# 11ethernetGbit.net
KiCad netlist of a schematic drawn in Altium Designer
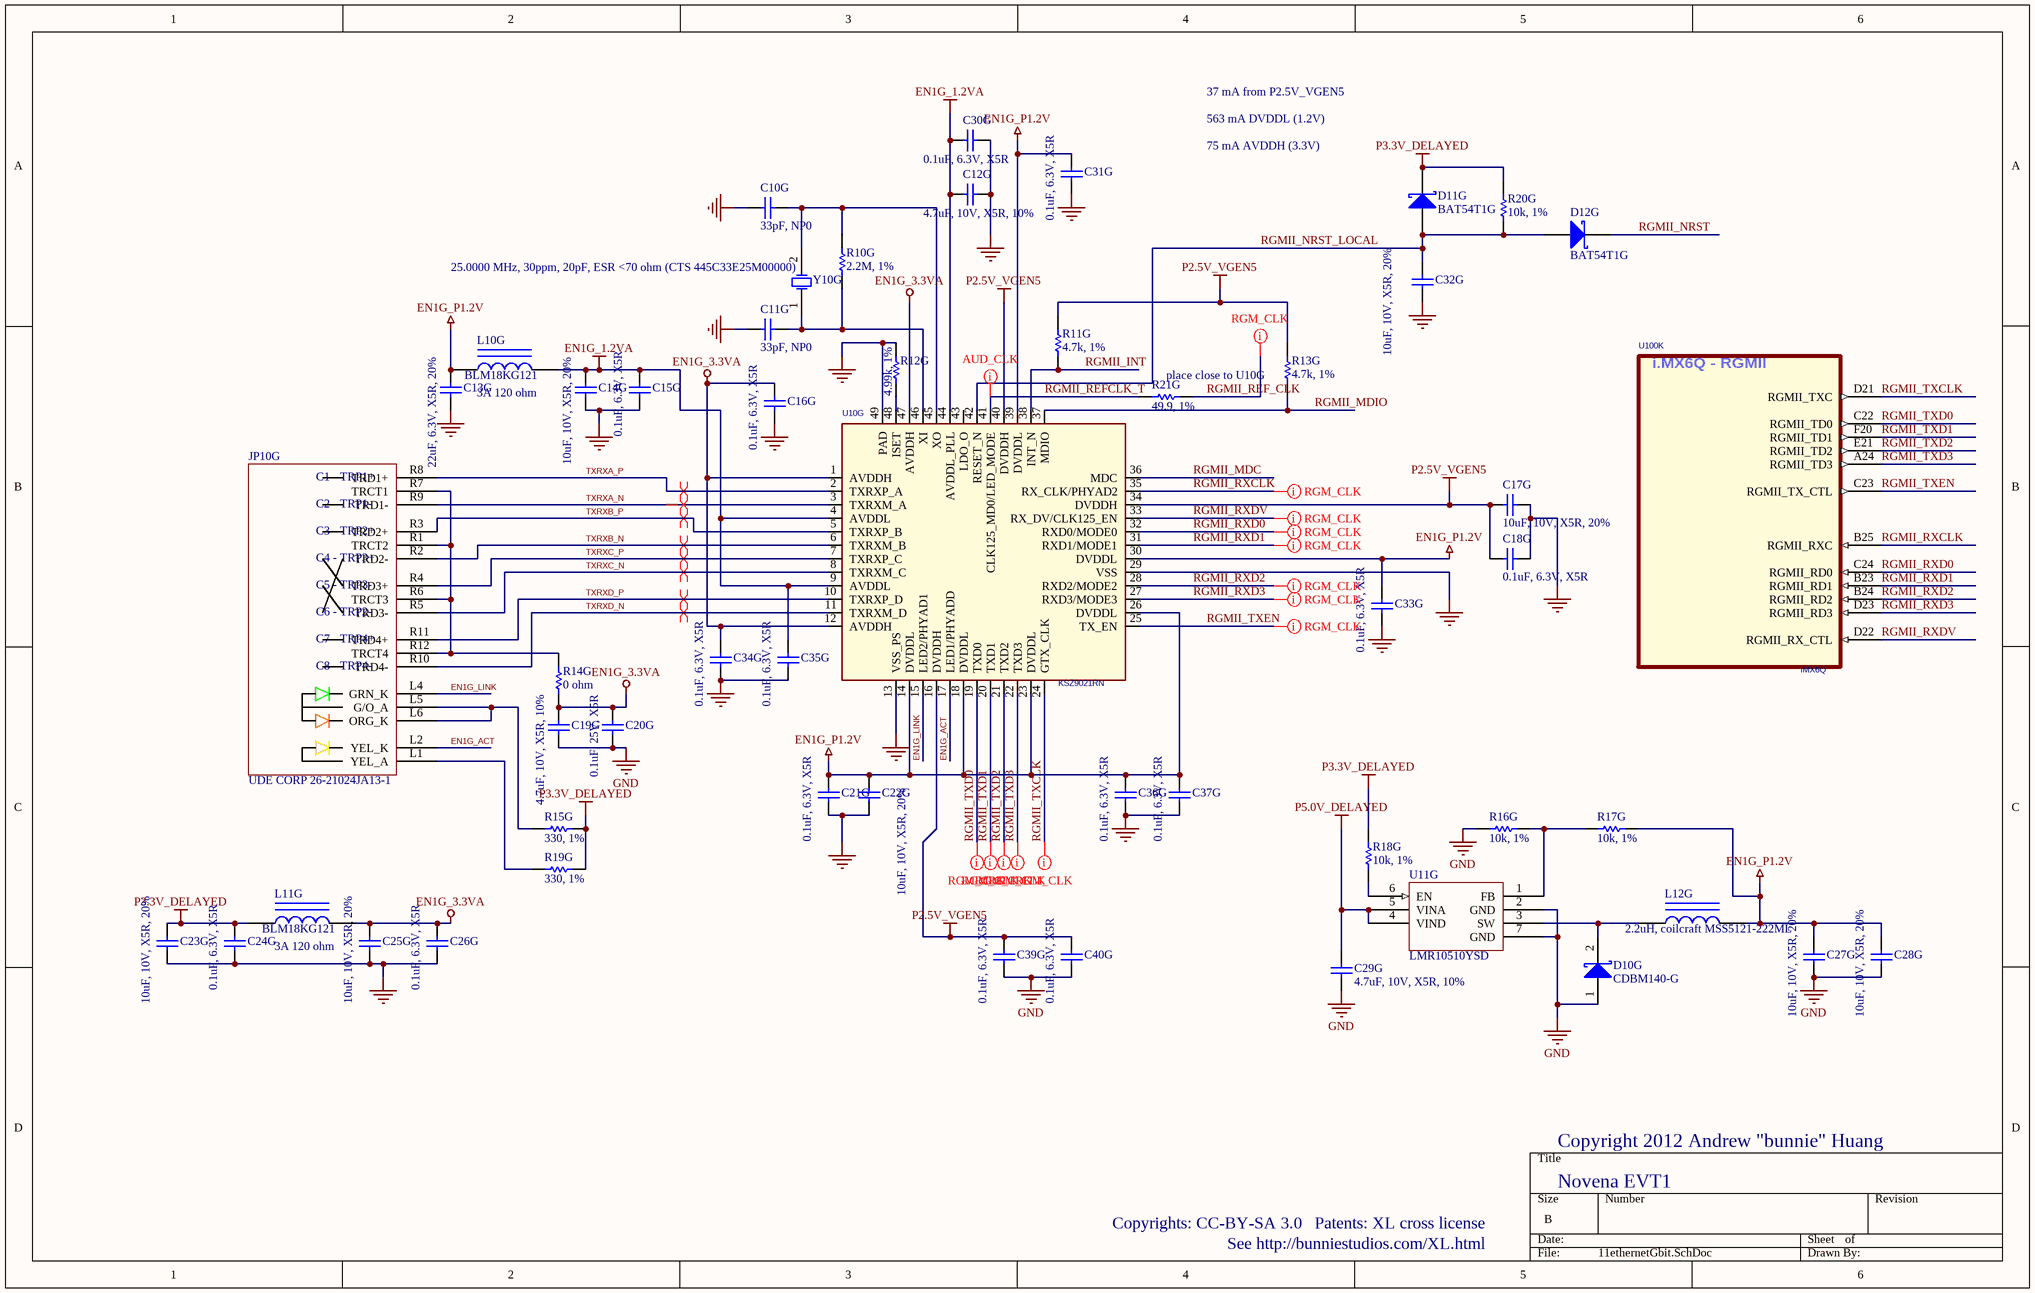
[diagram p0: 11ethernetGbit.SchDoc]

(export (version "E")
  (design (tool "Eeschema 10.0.6"))
  (components
    (comp (ref "C10G")
      (value "33pF, NP0")
      (footprint "CAPC1005N")
      (description "Capacitor (Semiconductor SIM Model)")
      (fields (field (name "PUBLISHER") "Altium Limited"))
      (libsource (lib "Miscellaneous Devices") (part "Cap Semi"))
    )
    (comp (ref "C11G")
      (value "33pF, NP0")
      (footprint "CAPC1005N")
      (description "Capacitor (Semiconductor SIM Model)")
      (fields (field (name "PUBLISHER") "Altium Limited"))
      (libsource (lib "Miscellaneous Devices") (part "Cap Semi"))
    )
    (comp (ref "C12G")
      (value "4.7uF, 10V, X5R, 10%")
      (footprint "CAPC1608N")
      (description "Capacitor (Semiconductor SIM Model)")
      (fields (field (name "PUBLISHER") "Altium Limited"))
      (libsource (lib "Miscellaneous Devices") (part "Cap Semi"))
    )
    (comp (ref "C13G")
      (value "22uF, 6.3V, X5R, 20%")
      (footprint "CAPC1608N_HD")
      (description "Capacitor (Semiconductor SIM Model)")
      (fields (field (name "PUBLISHER") "Altium Limited"))
      (libsource (lib "Miscellaneous Devices") (part "Cap Semi"))
    )
    (comp (ref "C14G")
      (value "10uF, 10V, X5R, 20%")
      (footprint "CAPC1608N")
      (description "Capacitor (Semiconductor SIM Model)")
      (fields (field (name "PUBLISHER") "Altium Limited"))
      (libsource (lib "Miscellaneous Devices") (part "Cap Semi"))
    )
    (comp (ref "C15G")
      (value "0.1uF, 6.3V, X5R")
      (footprint "CAPC0603N_B")
      (description "Capacitor (Semiconductor SIM Model)")
      (fields (field (name "PUBLISHER") "Altium Limited"))
      (libsource (lib "Miscellaneous Devices") (part "Cap Semi"))
    )
    (comp (ref "C16G")
      (value "0.1uF, 6.3V, X5R")
      (footprint "CAPC0603N_B")
      (description "Capacitor (Semiconductor SIM Model)")
      (fields (field (name "PUBLISHER") "Altium Limited"))
      (libsource (lib "Miscellaneous Devices") (part "Cap Semi"))
    )
    (comp (ref "C17G")
      (value "10uF, 10V, X5R, 20%")
      (footprint "CAPC1608N")
      (description "Capacitor (Semiconductor SIM Model)")
      (fields (field (name "PUBLISHER") "Altium Limited"))
      (libsource (lib "Miscellaneous Devices") (part "Cap Semi"))
    )
    (comp (ref "C18G")
      (value "0.1uF, 6.3V, X5R")
      (footprint "CAPC0603N_B")
      (description "Capacitor (Semiconductor SIM Model)")
      (fields (field (name "PUBLISHER") "Altium Limited"))
      (libsource (lib "Miscellaneous Devices") (part "Cap Semi"))
    )
    (comp (ref "C19G")
      (value "4.7uF, 10V, X5R, 10%")
      (footprint "CAPC1608N")
      (description "Capacitor (Semiconductor SIM Model)")
      (fields (field (name "PUBLISHER") "Altium Limited"))
      (libsource (lib "Miscellaneous Devices") (part "Cap Semi"))
    )
    (comp (ref "C20G")
      (value "0.1uF, 25V, X5R")
      (footprint "CAPC1005N")
      (description "Capacitor (Semiconductor SIM Model)")
      (fields (field (name "PUBLISHER") "Altium Limited"))
      (libsource (lib "Miscellaneous Devices") (part "Cap Semi"))
    )
    (comp (ref "C21G")
      (value "0.1uF, 6.3V, X5R")
      (footprint "CAPC0603N_B")
      (description "Capacitor (Semiconductor SIM Model)")
      (fields (field (name "PUBLISHER") "Altium Limited"))
      (libsource (lib "Miscellaneous Devices") (part "Cap Semi"))
    )
    (comp (ref "C22G")
      (value "10uF, 10V, X5R, 20%")
      (footprint "CAPC1608N")
      (description "Capacitor (Semiconductor SIM Model)")
      (fields (field (name "PUBLISHER") "Altium Limited"))
      (libsource (lib "Miscellaneous Devices") (part "Cap Semi"))
    )
    (comp (ref "C23G")
      (value "10uF, 10V, X5R, 20%")
      (footprint "CAPC1608N")
      (description "Capacitor (Semiconductor SIM Model)")
      (fields (field (name "PUBLISHER") "Altium Limited"))
      (libsource (lib "Miscellaneous Devices") (part "Cap Semi"))
    )
    (comp (ref "C24G")
      (value "0.1uF, 6.3V, X5R")
      (footprint "CAPC0603N_B")
      (description "Capacitor (Semiconductor SIM Model)")
      (fields (field (name "PUBLISHER") "Altium Limited"))
      (libsource (lib "Miscellaneous Devices") (part "Cap Semi"))
    )
    (comp (ref "C25G")
      (value "10uF, 10V, X5R, 20%")
      (footprint "CAPC1608N")
      (description "Capacitor (Semiconductor SIM Model)")
      (fields (field (name "PUBLISHER") "Altium Limited"))
      (libsource (lib "Miscellaneous Devices") (part "Cap Semi"))
    )
    (comp (ref "C26G")
      (value "0.1uF, 6.3V, X5R")
      (footprint "CAPC0603N_B")
      (description "Capacitor (Semiconductor SIM Model)")
      (fields (field (name "PUBLISHER") "Altium Limited"))
      (libsource (lib "Miscellaneous Devices") (part "Cap Semi"))
    )
    (comp (ref "C27G")
      (value "10uF, 10V, X5R, 20%")
      (footprint "CAPC1608N")
      (description "Capacitor (Semiconductor SIM Model)")
      (fields (field (name "PUBLISHER") "Altium Limited"))
      (libsource (lib "Miscellaneous Devices") (part "Cap Semi"))
    )
    (comp (ref "C28G")
      (value "10uF, 10V, X5R, 20%")
      (footprint "CAPC1608N")
      (description "Capacitor (Semiconductor SIM Model)")
      (fields (field (name "PUBLISHER") "Altium Limited"))
      (libsource (lib "Miscellaneous Devices") (part "Cap Semi"))
    )
    (comp (ref "C29G")
      (value "4.7uF, 10V, X5R, 10%")
      (footprint "CAPC1608N")
      (description "Capacitor (Semiconductor SIM Model)")
      (fields (field (name "PUBLISHER") "Altium Limited"))
      (libsource (lib "Miscellaneous Devices") (part "Cap Semi"))
    )
    (comp (ref "C30G")
      (value "0.1uF, 6.3V, X5R")
      (footprint "CAPC0603N_B")
      (description "Capacitor (Semiconductor SIM Model)")
      (fields (field (name "PUBLISHER") "Altium Limited"))
      (libsource (lib "Miscellaneous Devices") (part "Cap Semi"))
    )
    (comp (ref "C31G")
      (value "0.1uF, 6.3V, X5R")
      (footprint "CAPC0603N_B")
      (description "Capacitor (Semiconductor SIM Model)")
      (fields (field (name "PUBLISHER") "Altium Limited"))
      (libsource (lib "Miscellaneous Devices") (part "Cap Semi"))
    )
    (comp (ref "C32G")
      (value "10uF, 10V, X5R, 20%")
      (footprint "CAPC1608N")
      (description "Capacitor (Semiconductor SIM Model)")
      (fields (field (name "PUBLISHER") "Altium Limited"))
      (libsource (lib "Miscellaneous Devices") (part "Cap Semi"))
    )
    (comp (ref "C33G")
      (value "0.1uF, 6.3V, X5R")
      (footprint "CAPC0603N_B")
      (description "Capacitor (Semiconductor SIM Model)")
      (fields (field (name "PUBLISHER") "Altium Limited"))
      (libsource (lib "Miscellaneous Devices") (part "Cap Semi"))
    )
    (comp (ref "C34G")
      (value "0.1uF, 6.3V, X5R")
      (footprint "CAPC0603N_B")
      (description "Capacitor (Semiconductor SIM Model)")
      (fields (field (name "PUBLISHER") "Altium Limited"))
      (libsource (lib "Miscellaneous Devices") (part "Cap Semi"))
    )
    (comp (ref "C35G")
      (value "0.1uF, 6.3V, X5R")
      (footprint "CAPC0603N_B")
      (description "Capacitor (Semiconductor SIM Model)")
      (fields (field (name "PUBLISHER") "Altium Limited"))
      (libsource (lib "Miscellaneous Devices") (part "Cap Semi"))
    )
    (comp (ref "C36G")
      (value "0.1uF, 6.3V, X5R")
      (footprint "CAPC0603N_B")
      (description "Capacitor (Semiconductor SIM Model)")
      (fields (field (name "PUBLISHER") "Altium Limited"))
      (libsource (lib "Miscellaneous Devices") (part "Cap Semi"))
    )
    (comp (ref "C37G")
      (value "0.1uF, 6.3V, X5R")
      (footprint "CAPC0603N_B")
      (description "Capacitor (Semiconductor SIM Model)")
      (fields (field (name "PUBLISHER") "Altium Limited"))
      (libsource (lib "Miscellaneous Devices") (part "Cap Semi"))
    )
    (comp (ref "C39G")
      (value "0.1uF, 6.3V, X5R")
      (footprint "CAPC0603N_B")
      (description "Capacitor (Semiconductor SIM Model)")
      (fields (field (name "PUBLISHER") "Altium Limited"))
      (libsource (lib "Miscellaneous Devices") (part "Cap Semi"))
    )
    (comp (ref "C40G")
      (value "0.1uF, 6.3V, X5R")
      (footprint "CAPC0603N_B")
      (description "Capacitor (Semiconductor SIM Model)")
      (fields (field (name "PUBLISHER") "Altium Limited"))
      (libsource (lib "Miscellaneous Devices") (part "Cap Semi"))
    )
    (comp (ref "D10G")
      (value "CDBM140-G")
      (footprint "SOD123")
      (description "Schottky Diode")
      (fields (field (name "PUBLISHER") "Altium Limited"))
      (libsource (lib "Miscellaneous Devices") (part "D Schottky"))
    )
    (comp (ref "D11G")
      (value "BAT54T1G")
      (footprint "SOD123")
      (description "Schottky Diode")
      (fields (field (name "PUBLISHER") "Altium Limited"))
      (libsource (lib "") (part "D Schottky_1"))
    )
    (comp (ref "D12G")
      (value "BAT54T1G")
      (footprint "SOD123")
      (description "Schottky Diode")
      (fields (field (name "PUBLISHER") "Altium Limited"))
      (libsource (lib "") (part "D Schottky_1"))
    )
    (comp (ref "JP10G")
      (value "UDE CORP 26-21024JA13-1")
      (footprint "UDE_CORP_26-21024JA13-1")
      (description "10/100/1000BT + magnetics, symmetric, tab up, with LEDs")
      (libsource (lib "commonsch") (part "UDE_CORP_26-21024JA13-1"))
    )
    (comp (ref "L10G")
      (value "BLM18KG121")
      (footprint "INDC1608AN")
      (description "Magnetic-Core Inductor")
      (fields (field (name "ALTIUM_VALUE") "3A 120 ohm") (field (name "PUBLISHER") "Altium Limited"))
      (libsource (lib "Miscellaneous Devices") (part "Inductor Iron"))
    )
    (comp (ref "L11G")
      (value "BLM18KG121")
      (footprint "INDC1608AN")
      (description "Magnetic-Core Inductor")
      (fields (field (name "ALTIUM_VALUE") "3A 120 ohm") (field (name "PUBLISHER") "Altium Limited"))
      (libsource (lib "Miscellaneous Devices") (part "Inductor Iron"))
    )
    (comp (ref "L12G")
      (value "2.2uH, coilcraft MSS5121-222ML")
      (footprint "COILCRAFT_MSS5121")
      (description "Magnetic-Core Inductor")
      (fields (field (name "PUBLISHER") "Altium Limited"))
      (libsource (lib "Miscellaneous Devices") (part "Inductor Iron"))
    )
    (comp (ref "R10G")
      (value "2.2M, 1%")
      (footprint "RESC1005N")
      (description "Resistor")
      (fields (field (name "PUBLISHER") "Altium Limited"))
      (libsource (lib "Miscellaneous Devices") (part "Res1"))
    )
    (comp (ref "R11G")
      (value "4.7k, 1%")
      (footprint "RESC1005N")
      (description "Resistor")
      (fields (field (name "PUBLISHER") "Altium Limited"))
      (libsource (lib "Miscellaneous Devices") (part "Res1"))
    )
    (comp (ref "R12G")
      (value "4.99k, 1%")
      (footprint "RESC1005N")
      (description "Resistor")
      (fields (field (name "PUBLISHER") "Altium Limited"))
      (libsource (lib "Miscellaneous Devices") (part "Res1"))
    )
    (comp (ref "R13G")
      (value "4.7k, 1%")
      (footprint "RESC1005N")
      (description "Resistor")
      (fields (field (name "PUBLISHER") "Altium Limited"))
      (libsource (lib "Miscellaneous Devices") (part "Res1"))
    )
    (comp (ref "R14G")
      (value "0 ohm")
      (footprint "RESC1005N")
      (description "Resistor")
      (fields (field (name "PUBLISHER") "Altium Limited"))
      (libsource (lib "Miscellaneous Devices") (part "Res1"))
    )
    (comp (ref "R15G")
      (value "330, 1%")
      (footprint "RESC1005N")
      (description "Resistor")
      (fields (field (name "PUBLISHER") "Altium Limited"))
      (libsource (lib "Miscellaneous Devices") (part "Res1"))
    )
    (comp (ref "R16G")
      (value "10k, 1%")
      (footprint "RESC1005N")
      (description "Resistor")
      (fields (field (name "PUBLISHER") "Altium Limited"))
      (libsource (lib "Miscellaneous Devices") (part "Res1"))
    )
    (comp (ref "R17G")
      (value "10k, 1%")
      (footprint "RESC1005N")
      (description "Resistor")
      (fields (field (name "PUBLISHER") "Altium Limited"))
      (libsource (lib "Miscellaneous Devices") (part "Res1"))
    )
    (comp (ref "R18G")
      (value "10k, 1%")
      (footprint "RESC1005N")
      (description "Resistor")
      (fields (field (name "PUBLISHER") "Altium Limited"))
      (libsource (lib "Miscellaneous Devices") (part "Res1"))
    )
    (comp (ref "R19G")
      (value "330, 1%")
      (footprint "RESC1005N")
      (description "Resistor")
      (fields (field (name "PUBLISHER") "Altium Limited"))
      (libsource (lib "Miscellaneous Devices") (part "Res1"))
    )
    (comp (ref "R20G")
      (value "10k, 1%")
      (footprint "RESC1005N")
      (description "Resistor")
      (fields (field (name "PUBLISHER") "Altium Limited"))
      (libsource (lib "Miscellaneous Devices") (part "Res1"))
    )
    (comp (ref "R21G")
      (value "49.9, 1%")
      (footprint "RESC1005N")
      (description "Resistor")
      (fields (field (name "PUBLISHER") "Altium Limited"))
      (libsource (lib "Miscellaneous Devices") (part "Res1"))
    )
    (comp (ref "U10G")
      (value "KSZ9021RN")
      (footprint "MICREL_QFN48_EP")
      (description "Gigabit Ethernet PHY")
      (libsource (lib "*") (part "KSZ9021_0"))
    )
    (comp (ref "U11G")
      (value "LMR10510YSD")
      (footprint "SON95P300X300X80-7V")
      (description "NatSemi 1.5A step-down regulator in LLP")
      (libsource (lib "commonsch") (part "LMR10515XSD"))
    )
    (comp (ref "U100")
      (value "iMX6Q")
      (footprint "FREESCALE_BGA624C80P25X25_2100X2100X216")
      (description "PLACEHOLDER FOR FREESCALE PART NUMBER PMCIMX6Q6VV1A.")
      (libsource (lib "*") (part "PCIMX6Q6VV1A"))
    )
    (comp (ref "Y10G")
      (value "25.0000 MHz, 30ppm, 20pF, ESR <70 ohm (CTS 445C33E25M00000)")
      (footprint "NDK_NX5032A")
      (description "Crystal Oscillator")
      (fields (field (name "PUBLISHER") "Altium Limited"))
      (libsource (lib "Miscellaneous Devices") (part "XTAL"))
    )
  )
  (nets
    (net (code "1") (name "/EN1G_ACT") (class "Default")
      (node (ref "JP10G") (pin "L2") (pinfunction "YEL_K_L2") (pintype "passive"))
      (node (ref "U10G") (pin "17") (pinfunction "LED1/PHYADD_17") (pintype "passive"))
    )
    (net (code "2") (name "/EN1G_LINK") (class "Default")
      (node (ref "JP10G") (pin "L4") (pinfunction "GRN_K_L4") (pintype "passive"))
      (node (ref "U10G") (pin "15") (pinfunction "LED2/PHYAD1_15") (pintype "passive"))
    )
    (net (code "3") (name "/RGMII_INT") (class "Default")
      (node (ref "R11G") (pin "1") (pinfunction "1_1") (pintype "passive"))
      (node (ref "U10G") (pin "38") (pinfunction "INT_N_38") (pintype "passive"))
    )
    (net (code "4") (name "/RGMII_MDC") (class "Default")
      (node (ref "U10G") (pin "36") (pinfunction "MDC_36") (pintype "passive"))
    )
    (net (code "5") (name "/RGMII_MDIO") (class "Default")
      (node (ref "R13G") (pin "1") (pinfunction "1_1") (pintype "passive"))
      (node (ref "U10G") (pin "37") (pinfunction "MDIO_37") (pintype "passive"))
    )
    (net (code "6") (name "/RGMII_NRST") (class "Default")
      (node (ref "D12G") (pin "2") (pinfunction "K_2") (pintype "passive"))
    )
    (net (code "7") (name "/RGMII_NRST_LOCAL") (class "Default")
      (node (ref "C32G") (pin "1") (pinfunction "1_1") (pintype "passive"))
      (node (ref "D11G") (pin "1") (pinfunction "A_1") (pintype "passive"))
      (node (ref "D12G") (pin "1") (pinfunction "A_1") (pintype "passive"))
      (node (ref "R20G") (pin "1") (pinfunction "1_1") (pintype "passive"))
      (node (ref "U10G") (pin "42") (pinfunction "RESET_N_42") (pintype "passive"))
    )
    (net (code "8") (name "/RGMII_REFCLK_T") (class "Default")
      (node (ref "R21G") (pin "1") (pinfunction "1_1") (pintype "passive"))
      (node (ref "U10G") (pin "41") (pinfunction "CLK125_MD0/LED_MODE_41") (pintype "passive"))
    )
    (net (code "9") (name "/RGMII_REF_CLK") (class "Default")
      (node (ref "R21G") (pin "2") (pinfunction "2_2") (pintype "passive"))
    )
    (net (code "10") (name "/RGMII_RXCLK") (class "Default")
      (node (ref "U100") (pin "B25") (pinfunction "RGMII_RXC_B25") (pintype "input"))
      (node (ref "U10G") (pin "35") (pinfunction "RX_CLK/PHYAD2_35") (pintype "passive"))
    )
    (net (code "11") (name "/RGMII_RXD0") (class "Default")
      (node (ref "U100") (pin "C24") (pinfunction "RGMII_RD0_C24") (pintype "input"))
      (node (ref "U10G") (pin "32") (pinfunction "RXD0/MODE0_32") (pintype "passive"))
    )
    (net (code "12") (name "/RGMII_RXD1") (class "Default")
      (node (ref "U100") (pin "B23") (pinfunction "RGMII_RD1_B23") (pintype "input"))
      (node (ref "U10G") (pin "31") (pinfunction "RXD1/MODE1_31") (pintype "passive"))
    )
    (net (code "13") (name "/RGMII_RXD2") (class "Default")
      (node (ref "U100") (pin "B24") (pinfunction "RGMII_RD2_B24") (pintype "input"))
      (node (ref "U10G") (pin "28") (pinfunction "RXD2/MODE2_28") (pintype "passive"))
    )
    (net (code "14") (name "/RGMII_RXD3") (class "Default")
      (node (ref "U100") (pin "D23") (pinfunction "RGMII_RD3_D23") (pintype "input"))
      (node (ref "U10G") (pin "27") (pinfunction "RXD3/MODE3_27") (pintype "passive"))
    )
    (net (code "15") (name "/RGMII_RXDV") (class "Default")
      (node (ref "U100") (pin "D22") (pinfunction "RGMII_RX_CTL_D22") (pintype "input"))
      (node (ref "U10G") (pin "33") (pinfunction "RX_DV/CLK125_EN_33") (pintype "passive"))
    )
    (net (code "16") (name "/RGMII_TXCLK") (class "Default")
      (node (ref "U100") (pin "D21") (pinfunction "RGMII_TXC_D21") (pintype "output"))
      (node (ref "U10G") (pin "24") (pinfunction "GTX_CLK_24") (pintype "passive"))
    )
    (net (code "17") (name "/RGMII_TXD0") (class "Default")
      (node (ref "U100") (pin "C22") (pinfunction "RGMII_TD0_C22") (pintype "output"))
      (node (ref "U10G") (pin "19") (pinfunction "TXD0_19") (pintype "passive"))
    )
    (net (code "18") (name "/RGMII_TXD1") (class "Default")
      (node (ref "U100") (pin "F20") (pinfunction "RGMII_TD1_F20") (pintype "output"))
      (node (ref "U10G") (pin "20") (pinfunction "TXD1_20") (pintype "passive"))
    )
    (net (code "19") (name "/RGMII_TXD2") (class "Default")
      (node (ref "U100") (pin "E21") (pinfunction "RGMII_TD2_E21") (pintype "output"))
      (node (ref "U10G") (pin "21") (pinfunction "TXD2_21") (pintype "passive"))
    )
    (net (code "20") (name "/RGMII_TXD3") (class "Default")
      (node (ref "U100") (pin "A24") (pinfunction "RGMII_TD3_A24") (pintype "output"))
      (node (ref "U10G") (pin "22") (pinfunction "TXD3_22") (pintype "passive"))
    )
    (net (code "21") (name "/RGMII_TXEN") (class "Default")
      (node (ref "U100") (pin "C23") (pinfunction "RGMII_TX_CTL_C23") (pintype "output"))
      (node (ref "U10G") (pin "25") (pinfunction "TX_EN_25") (pintype "passive"))
    )
    (net (code "22") (name "/TXRXA_N") (class "Default")
      (node (ref "JP10G") (pin "R9") (pinfunction "TRD1-_R9") (pintype "passive"))
      (node (ref "U10G") (pin "3") (pinfunction "TXRXM_A_3") (pintype "passive"))
    )
    (net (code "23") (name "/TXRXA_P") (class "Default")
      (node (ref "JP10G") (pin "R8") (pinfunction "TRD1+_R8") (pintype "passive"))
      (node (ref "U10G") (pin "2") (pinfunction "TXRXP_A_2") (pintype "passive"))
    )
    (net (code "24") (name "/TXRXB_N") (class "Default")
      (node (ref "JP10G") (pin "R2") (pinfunction "TRD2-_R2") (pintype "passive"))
      (node (ref "U10G") (pin "6") (pinfunction "TXRXM_B_6") (pintype "passive"))
    )
    (net (code "25") (name "/TXRXB_P") (class "Default")
      (node (ref "JP10G") (pin "R3") (pinfunction "TRD2+_R3") (pintype "passive"))
      (node (ref "U10G") (pin "5") (pinfunction "TXRXP_B_5") (pintype "passive"))
    )
    (net (code "26") (name "/TXRXC_N") (class "Default")
      (node (ref "JP10G") (pin "R5") (pinfunction "TRD3-_R5") (pintype "passive"))
      (node (ref "U10G") (pin "8") (pinfunction "TXRXM_C_8") (pintype "passive"))
    )
    (net (code "27") (name "/TXRXC_P") (class "Default")
      (node (ref "JP10G") (pin "R4") (pinfunction "TRD3+_R4") (pintype "passive"))
      (node (ref "U10G") (pin "7") (pinfunction "TXRXP_C_7") (pintype "passive"))
    )
    (net (code "28") (name "/TXRXD_N") (class "Default")
      (node (ref "JP10G") (pin "R10") (pinfunction "TRD4-_R10") (pintype "passive"))
      (node (ref "U10G") (pin "11") (pinfunction "TXRXM_D_11") (pintype "passive"))
    )
    (net (code "29") (name "/TXRXD_P") (class "Default")
      (node (ref "JP10G") (pin "R11") (pinfunction "TRD4+_R11") (pintype "passive"))
      (node (ref "U10G") (pin "10") (pinfunction "TXRXP_D_10") (pintype "passive"))
    )
    (net (code "30") (name "EN1G_1.2VA") (class "Default")
      (node (ref "C12G") (pin "1") (pinfunction "1_1") (pintype "passive"))
      (node (ref "C14G") (pin "1") (pinfunction "1_1") (pintype "passive"))
      (node (ref "C15G") (pin "1") (pinfunction "1_1") (pintype "passive"))
      (node (ref "C30G") (pin "2") (pinfunction "2_2") (pintype "passive"))
      (node (ref "C35G") (pin "1") (pinfunction "1_1") (pintype "passive"))
      (node (ref "L10G") (pin "2") (pinfunction "2_2") (pintype "passive"))
      (node (ref "U10G") (pin "4") (pinfunction "AVDDL_4") (pintype "passive"))
      (node (ref "U10G") (pin "44") (pinfunction "AVDDL_PLL_44") (pintype "passive"))
      (node (ref "U10G") (pin "9") (pinfunction "AVDDL_9") (pintype "passive"))
    )
    (net (code "31") (name "EN1G_3.3VA") (class "Default")
      (node (ref "C16G") (pin "1") (pinfunction "1_1") (pintype "passive"))
      (node (ref "C19G") (pin "1") (pinfunction "1_1") (pintype "passive"))
      (node (ref "C20G") (pin "1") (pinfunction "1_1") (pintype "passive"))
      (node (ref "C25G") (pin "1") (pinfunction "1_1") (pintype "passive"))
      (node (ref "C26G") (pin "1") (pinfunction "1_1") (pintype "passive"))
      (node (ref "C34G") (pin "1") (pinfunction "1_1") (pintype "passive"))
      (node (ref "L11G") (pin "2") (pinfunction "2_2") (pintype "passive"))
      (node (ref "R14G") (pin "2") (pinfunction "2_2") (pintype "passive"))
      (node (ref "U10G") (pin "1") (pinfunction "AVDDH_1") (pintype "passive"))
      (node (ref "U10G") (pin "12") (pinfunction "AVDDH_12") (pintype "passive"))
      (node (ref "U10G") (pin "47") (pinfunction "AVDDH_47") (pintype "passive"))
    )
    (net (code "32") (name "EN1G_P1.2V") (class "Default")
      (node (ref "C13G") (pin "1") (pinfunction "1_1") (pintype "passive"))
      (node (ref "C21G") (pin "1") (pinfunction "1_1") (pintype "passive"))
      (node (ref "C22G") (pin "1") (pinfunction "1_1") (pintype "passive"))
      (node (ref "C27G") (pin "2") (pinfunction "2_2") (pintype "passive"))
      (node (ref "C28G") (pin "2") (pinfunction "2_2") (pintype "passive"))
      (node (ref "C31G") (pin "1") (pinfunction "1_1") (pintype "passive"))
      (node (ref "C33G") (pin "1") (pinfunction "1_1") (pintype "passive"))
      (node (ref "C36G") (pin "1") (pinfunction "1_1") (pintype "passive"))
      (node (ref "C37G") (pin "1") (pinfunction "1_1") (pintype "passive"))
      (node (ref "L10G") (pin "1") (pinfunction "1_1") (pintype "passive"))
      (node (ref "L12G") (pin "2") (pinfunction "2_2") (pintype "passive"))
      (node (ref "R17G") (pin "1") (pinfunction "1_1") (pintype "passive"))
      (node (ref "U10G") (pin "14") (pinfunction "DVDDL_14") (pintype "passive"))
      (node (ref "U10G") (pin "18") (pinfunction "DVDDL_18") (pintype "passive"))
      (node (ref "U10G") (pin "23") (pinfunction "DVDDL_23") (pintype "passive"))
      (node (ref "U10G") (pin "26") (pinfunction "DVDDL_26") (pintype "passive"))
      (node (ref "U10G") (pin "30") (pinfunction "DVDDL_30") (pintype "passive"))
      (node (ref "U10G") (pin "39") (pinfunction "DVDDL_39") (pintype "passive"))
    )
    (net (code "33") (name "GND") (class "Default")
      (node (ref "C10G") (pin "1") (pinfunction "1_1") (pintype "passive"))
      (node (ref "C11G") (pin "1") (pinfunction "1_1") (pintype "passive"))
      (node (ref "C12G") (pin "2") (pinfunction "2_2") (pintype "passive"))
      (node (ref "C13G") (pin "2") (pinfunction "2_2") (pintype "passive"))
      (node (ref "C14G") (pin "2") (pinfunction "2_2") (pintype "passive"))
      (node (ref "C15G") (pin "2") (pinfunction "2_2") (pintype "passive"))
      (node (ref "C16G") (pin "2") (pinfunction "2_2") (pintype "passive"))
      (node (ref "C17G") (pin "2") (pinfunction "2_2") (pintype "passive"))
      (node (ref "C18G") (pin "2") (pinfunction "2_2") (pintype "passive"))
      (node (ref "C19G") (pin "2") (pinfunction "2_2") (pintype "passive"))
      (node (ref "C20G") (pin "2") (pinfunction "2_2") (pintype "passive"))
      (node (ref "C21G") (pin "2") (pinfunction "2_2") (pintype "passive"))
      (node (ref "C22G") (pin "2") (pinfunction "2_2") (pintype "passive"))
      (node (ref "C23G") (pin "2") (pinfunction "2_2") (pintype "passive"))
      (node (ref "C24G") (pin "2") (pinfunction "2_2") (pintype "passive"))
      (node (ref "C25G") (pin "2") (pinfunction "2_2") (pintype "passive"))
      (node (ref "C26G") (pin "2") (pinfunction "2_2") (pintype "passive"))
      (node (ref "C27G") (pin "1") (pinfunction "1_1") (pintype "passive"))
      (node (ref "C28G") (pin "1") (pinfunction "1_1") (pintype "passive"))
      (node (ref "C29G") (pin "2") (pinfunction "2_2") (pintype "passive"))
      (node (ref "C30G") (pin "1") (pinfunction "1_1") (pintype "passive"))
      (node (ref "C31G") (pin "2") (pinfunction "2_2") (pintype "passive"))
      (node (ref "C32G") (pin "2") (pinfunction "2_2") (pintype "passive"))
      (node (ref "C33G") (pin "2") (pinfunction "2_2") (pintype "passive"))
      (node (ref "C34G") (pin "2") (pinfunction "2_2") (pintype "passive"))
      (node (ref "C35G") (pin "2") (pinfunction "2_2") (pintype "passive"))
      (node (ref "C36G") (pin "2") (pinfunction "2_2") (pintype "passive"))
      (node (ref "C37G") (pin "2") (pinfunction "2_2") (pintype "passive"))
      (node (ref "C39G") (pin "2") (pinfunction "2_2") (pintype "passive"))
      (node (ref "C40G") (pin "2") (pinfunction "2_2") (pintype "passive"))
      (node (ref "D10G") (pin "1") (pinfunction "A_1") (pintype "passive"))
      (node (ref "R12G") (pin "2") (pinfunction "2_2") (pintype "passive"))
      (node (ref "R16G") (pin "2") (pinfunction "2_2") (pintype "passive"))
      (node (ref "U10G") (pin "13") (pinfunction "VSS_PS_13") (pintype "passive"))
      (node (ref "U10G") (pin "29") (pinfunction "VSS_29") (pintype "passive"))
      (node (ref "U10G") (pin "49") (pinfunction "PAD_49") (pintype "passive"))
      (node (ref "U11G") (pin "2") (pinfunction "GND_2") (pintype "power_in"))
      (node (ref "U11G") (pin "7") (pinfunction "GND_7") (pintype "power_in"))
    )
    (net (code "34") (name "Net-(D10G-K)") (class "Default")
      (node (ref "D10G") (pin "2") (pinfunction "K_2") (pintype "passive"))
      (node (ref "L12G") (pin "1") (pinfunction "1_1") (pintype "passive"))
      (node (ref "U11G") (pin "3") (pinfunction "SW_3") (pintype "passive"))
    )
    (net (code "35") (name "Net-(JP10G-G{slash}O_A)") (class "Default")
      (node (ref "JP10G") (pin "L5") (pinfunction "G/O_A_L5") (pintype "passive"))
      (node (ref "JP10G") (pin "L6") (pinfunction "ORG_K_L6") (pintype "passive"))
      (node (ref "R15G") (pin "1") (pinfunction "1_1") (pintype "passive"))
    )
    (net (code "36") (name "Net-(JP10G-TRCT1)") (class "Default")
      (node (ref "JP10G") (pin "R1") (pinfunction "TRCT2_R1") (pintype "passive"))
      (node (ref "JP10G") (pin "R12") (pinfunction "TRCT4_R12") (pintype "passive"))
      (node (ref "JP10G") (pin "R6") (pinfunction "TRCT3_R6") (pintype "passive"))
      (node (ref "JP10G") (pin "R7") (pinfunction "TRCT1_R7") (pintype "passive"))
      (node (ref "R14G") (pin "1") (pinfunction "1_1") (pintype "passive"))
    )
    (net (code "37") (name "Net-(JP10G-YEL_A)") (class "Default")
      (node (ref "JP10G") (pin "L1") (pinfunction "YEL_A_L1") (pintype "passive"))
      (node (ref "R19G") (pin "1") (pinfunction "1_1") (pintype "passive"))
    )
    (net (code "38") (name "Net-(U10G-ISET)") (class "Default")
      (node (ref "R12G") (pin "1") (pinfunction "1_1") (pintype "passive"))
      (node (ref "U10G") (pin "48") (pinfunction "ISET_48") (pintype "passive"))
    )
    (net (code "39") (name "Net-(U10G-XI)") (class "Default")
      (node (ref "C11G") (pin "2") (pinfunction "2_2") (pintype "passive"))
      (node (ref "R10G") (pin "2") (pinfunction "2_2") (pintype "passive"))
      (node (ref "U10G") (pin "46") (pinfunction "XI_46") (pintype "passive"))
      (node (ref "Y10G") (pin "1") (pinfunction "OSC1_1") (pintype "passive"))
    )
    (net (code "40") (name "Net-(U10G-XO)") (class "Default")
      (node (ref "C10G") (pin "2") (pinfunction "2_2") (pintype "passive"))
      (node (ref "R10G") (pin "1") (pinfunction "1_1") (pintype "passive"))
      (node (ref "U10G") (pin "45") (pinfunction "XO_45") (pintype "passive"))
      (node (ref "Y10G") (pin "2") (pinfunction "OSC2_2") (pintype "passive"))
    )
    (net (code "41") (name "Net-(U11G-EN)") (class "Default")
      (node (ref "R18G") (pin "1") (pinfunction "1_1") (pintype "passive"))
      (node (ref "U11G") (pin "6") (pinfunction "EN_6") (pintype "input"))
    )
    (net (code "42") (name "Net-(U11G-FB)") (class "Default")
      (node (ref "R16G") (pin "1") (pinfunction "1_1") (pintype "passive"))
      (node (ref "R17G") (pin "2") (pinfunction "2_2") (pintype "passive"))
      (node (ref "U11G") (pin "1") (pinfunction "FB_1") (pintype "passive"))
    )
    (net (code "43") (name "P2.5V_VGEN5") (class "Default")
      (node (ref "C17G") (pin "1") (pinfunction "1_1") (pintype "passive"))
      (node (ref "C18G") (pin "1") (pinfunction "1_1") (pintype "passive"))
      (node (ref "C39G") (pin "1") (pinfunction "1_1") (pintype "passive"))
      (node (ref "C40G") (pin "1") (pinfunction "1_1") (pintype "passive"))
      (node (ref "R11G") (pin "2") (pinfunction "2_2") (pintype "passive"))
      (node (ref "R13G") (pin "2") (pinfunction "2_2") (pintype "passive"))
      (node (ref "U10G") (pin "16") (pinfunction "DVDDH_16") (pintype "passive"))
      (node (ref "U10G") (pin "34") (pinfunction "DVDDH_34") (pintype "passive"))
      (node (ref "U10G") (pin "40") (pinfunction "DVDDH_40") (pintype "passive"))
    )
    (net (code "44") (name "P3.3V_DELAYED") (class "Default")
      (node (ref "C23G") (pin "1") (pinfunction "1_1") (pintype "passive"))
      (node (ref "C24G") (pin "1") (pinfunction "1_1") (pintype "passive"))
      (node (ref "D11G") (pin "2") (pinfunction "K_2") (pintype "passive"))
      (node (ref "L11G") (pin "1") (pinfunction "1_1") (pintype "passive"))
      (node (ref "R15G") (pin "2") (pinfunction "2_2") (pintype "passive"))
      (node (ref "R18G") (pin "2") (pinfunction "2_2") (pintype "passive"))
      (node (ref "R19G") (pin "2") (pinfunction "2_2") (pintype "passive"))
      (node (ref "R20G") (pin "2") (pinfunction "2_2") (pintype "passive"))
    )
    (net (code "45") (name "P5.0V_DELAYED") (class "Default")
      (node (ref "C29G") (pin "1") (pinfunction "1_1") (pintype "passive"))
      (node (ref "U11G") (pin "4") (pinfunction "VIND_4") (pintype "power_in"))
      (node (ref "U11G") (pin "5") (pinfunction "VINA_5") (pintype "power_in"))
    )
    (net (code "46") (name "unconnected-(U10G-LDO_O-Pad43)") (class "Default")
      (node (ref "U10G") (pin "43") (pinfunction "LDO_O_43") (pintype "passive"))
    )
  )
)
